# ZMOD4510.net
KiCad netlist of a schematic drawn in EAGLE
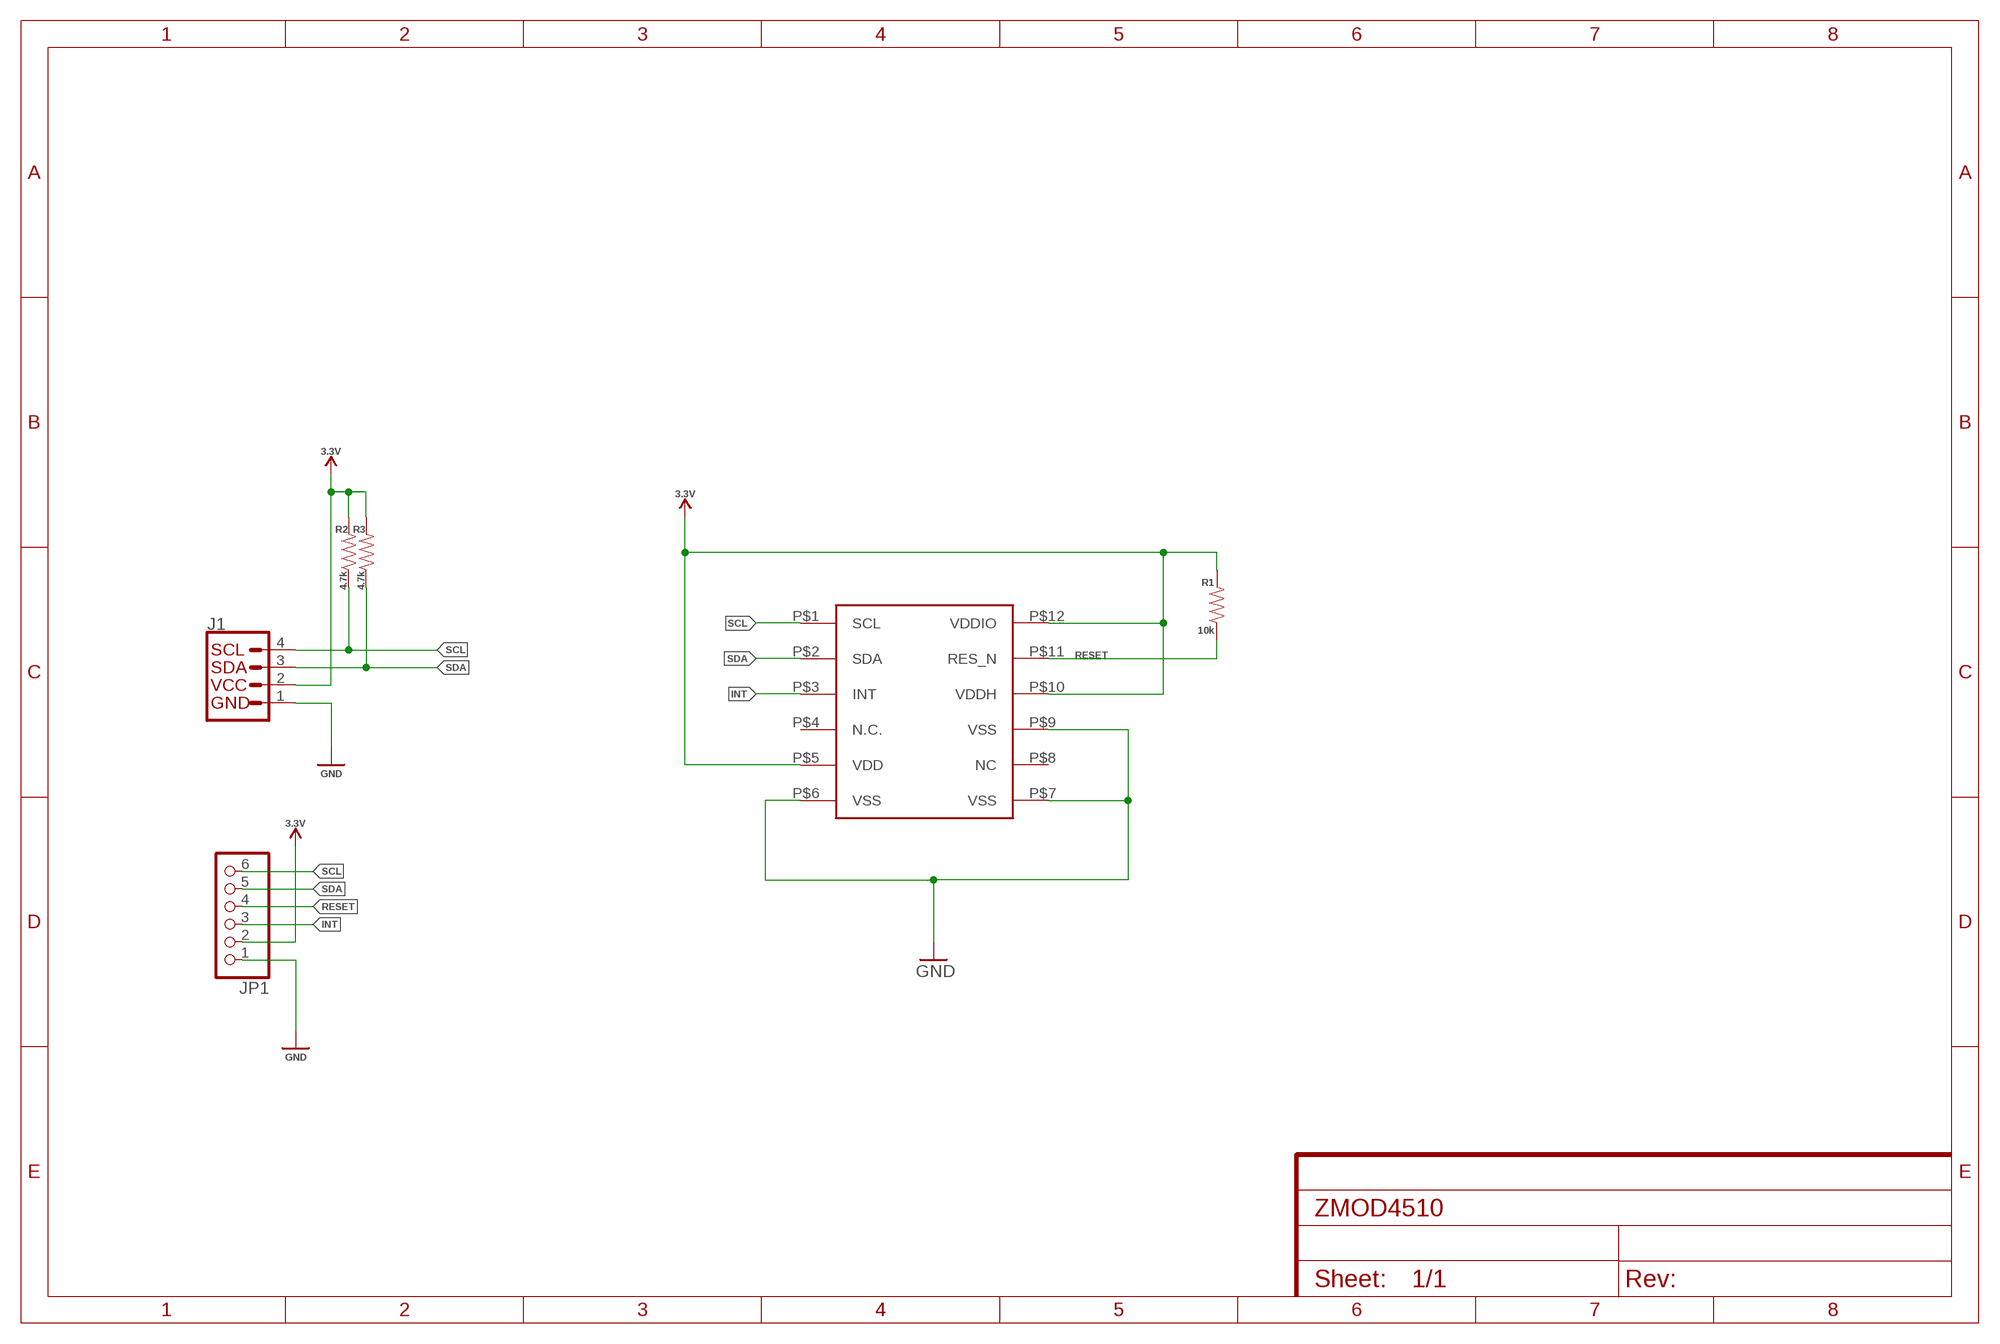
[diagram p0: schematic, sheet 1]

(export (version "E")
  (design (tool "Eeschema 10.0.6"))
  (components
    (comp (ref "J1")
      (value "QWIIC_CONNECTORJS-1MM")
      (footprint "eagle-import:1X04_1MM_RA")
      (libsource (lib "eagle-import") (part "QWIIC_CONNECTORJS-1MM"))
    )
    (comp (ref "JP1")
      (value "PINHD-1X6")
      (footprint "eagle-import:1X06")
      (libsource (lib "eagle-import") (part "PINHD-1X6"))
    )
    (comp (ref "R1")
      (value "10k")
      (footprint "eagle-import:0603")
      (libsource (lib "eagle-import") (part "10KOHM-0603-1/10W-1%"))
    )
    (comp (ref "R2")
      (value "4.7k")
      (footprint "eagle-import:0603")
      (libsource (lib "eagle-import") (part "4.7KOHM-0603-1/10W-1%"))
    )
    (comp (ref "R3")
      (value "4.7k")
      (footprint "eagle-import:0603")
      (libsource (lib "eagle-import") (part "4.7KOHM-0603-1/10W-1%"))
    )
    (comp (ref "U1")
      (value "ZMOD4510")
      (footprint "eagle-import:ZMOD4510")
      (libsource (lib "eagle-import") (part "ZMOD4510"))
    )
  )
  (nets
    (net (code "1") (name "3.3V") (class "Default")
      (node (ref "J1") (pin "2") (pinfunction "2_2") (pintype "power_in"))
      (node (ref "JP1") (pin "2") (pinfunction "2_2") (pintype "passive"))
      (node (ref "R1") (pin "2") (pinfunction "2_2") (pintype "passive"))
      (node (ref "R2") (pin "2") (pinfunction "2_2") (pintype "passive"))
      (node (ref "R3") (pin "2") (pinfunction "2_2") (pintype "passive"))
      (node (ref "U1") (pin "P$10") (pinfunction "VDDH_P$10") (pintype "bidirectional"))
      (node (ref "U1") (pin "P$12") (pinfunction "VDDIO_P$12") (pintype "bidirectional"))
      (node (ref "U1") (pin "P$5") (pinfunction "VDD_P$5") (pintype "bidirectional"))
    )
    (net (code "2") (name "GND") (class "Default")
      (node (ref "J1") (pin "1") (pinfunction "1_1") (pintype "power_in"))
      (node (ref "JP1") (pin "1") (pinfunction "1_1") (pintype "passive"))
      (node (ref "U1") (pin "P$6") (pinfunction "VSS_P$6") (pintype "bidirectional"))
      (node (ref "U1") (pin "P$7") (pinfunction "VSS_P$7") (pintype "bidirectional"))
      (node (ref "U1") (pin "P$9") (pinfunction "VSS_P$9") (pintype "bidirectional"))
    )
    (net (code "3") (name "INT") (class "Default")
      (node (ref "JP1") (pin "3") (pinfunction "3_3") (pintype "passive"))
      (node (ref "U1") (pin "P$3") (pinfunction "INT_P$3") (pintype "bidirectional"))
    )
    (net (code "4") (name "RESET") (class "Default")
      (node (ref "JP1") (pin "4") (pinfunction "4_4") (pintype "passive"))
      (node (ref "R1") (pin "1") (pinfunction "1_1") (pintype "passive"))
      (node (ref "U1") (pin "P$11") (pinfunction "RES_N_P$11") (pintype "bidirectional"))
    )
    (net (code "5") (name "SCL") (class "Default")
      (node (ref "J1") (pin "4") (pinfunction "4_4") (pintype "passive"))
      (node (ref "JP1") (pin "6") (pinfunction "6_6") (pintype "passive"))
      (node (ref "R2") (pin "1") (pinfunction "1_1") (pintype "passive"))
      (node (ref "U1") (pin "P$1") (pinfunction "SCL_P$1") (pintype "bidirectional"))
    )
    (net (code "6") (name "SDA") (class "Default")
      (node (ref "J1") (pin "3") (pinfunction "3_3") (pintype "passive"))
      (node (ref "JP1") (pin "5") (pinfunction "5_5") (pintype "passive"))
      (node (ref "R3") (pin "1") (pinfunction "1_1") (pintype "passive"))
      (node (ref "U1") (pin "P$2") (pinfunction "SDA_P$2") (pintype "bidirectional"))
    )
    (net (code "7") (name "unconnected-(U1-N.C.-PadP$4)") (class "Default")
      (node (ref "U1") (pin "P$4") (pinfunction "N.C._P$4") (pintype "no_connect"))
    )
    (net (code "8") (name "unconnected-(U1-NC-PadP$8)") (class "Default")
      (node (ref "U1") (pin "P$8") (pinfunction "NC_P$8") (pintype "no_connect"))
    )
  )
)
